# FPGA_FPGA.net
KiCad netlist of a schematic drawn in Altium Designer
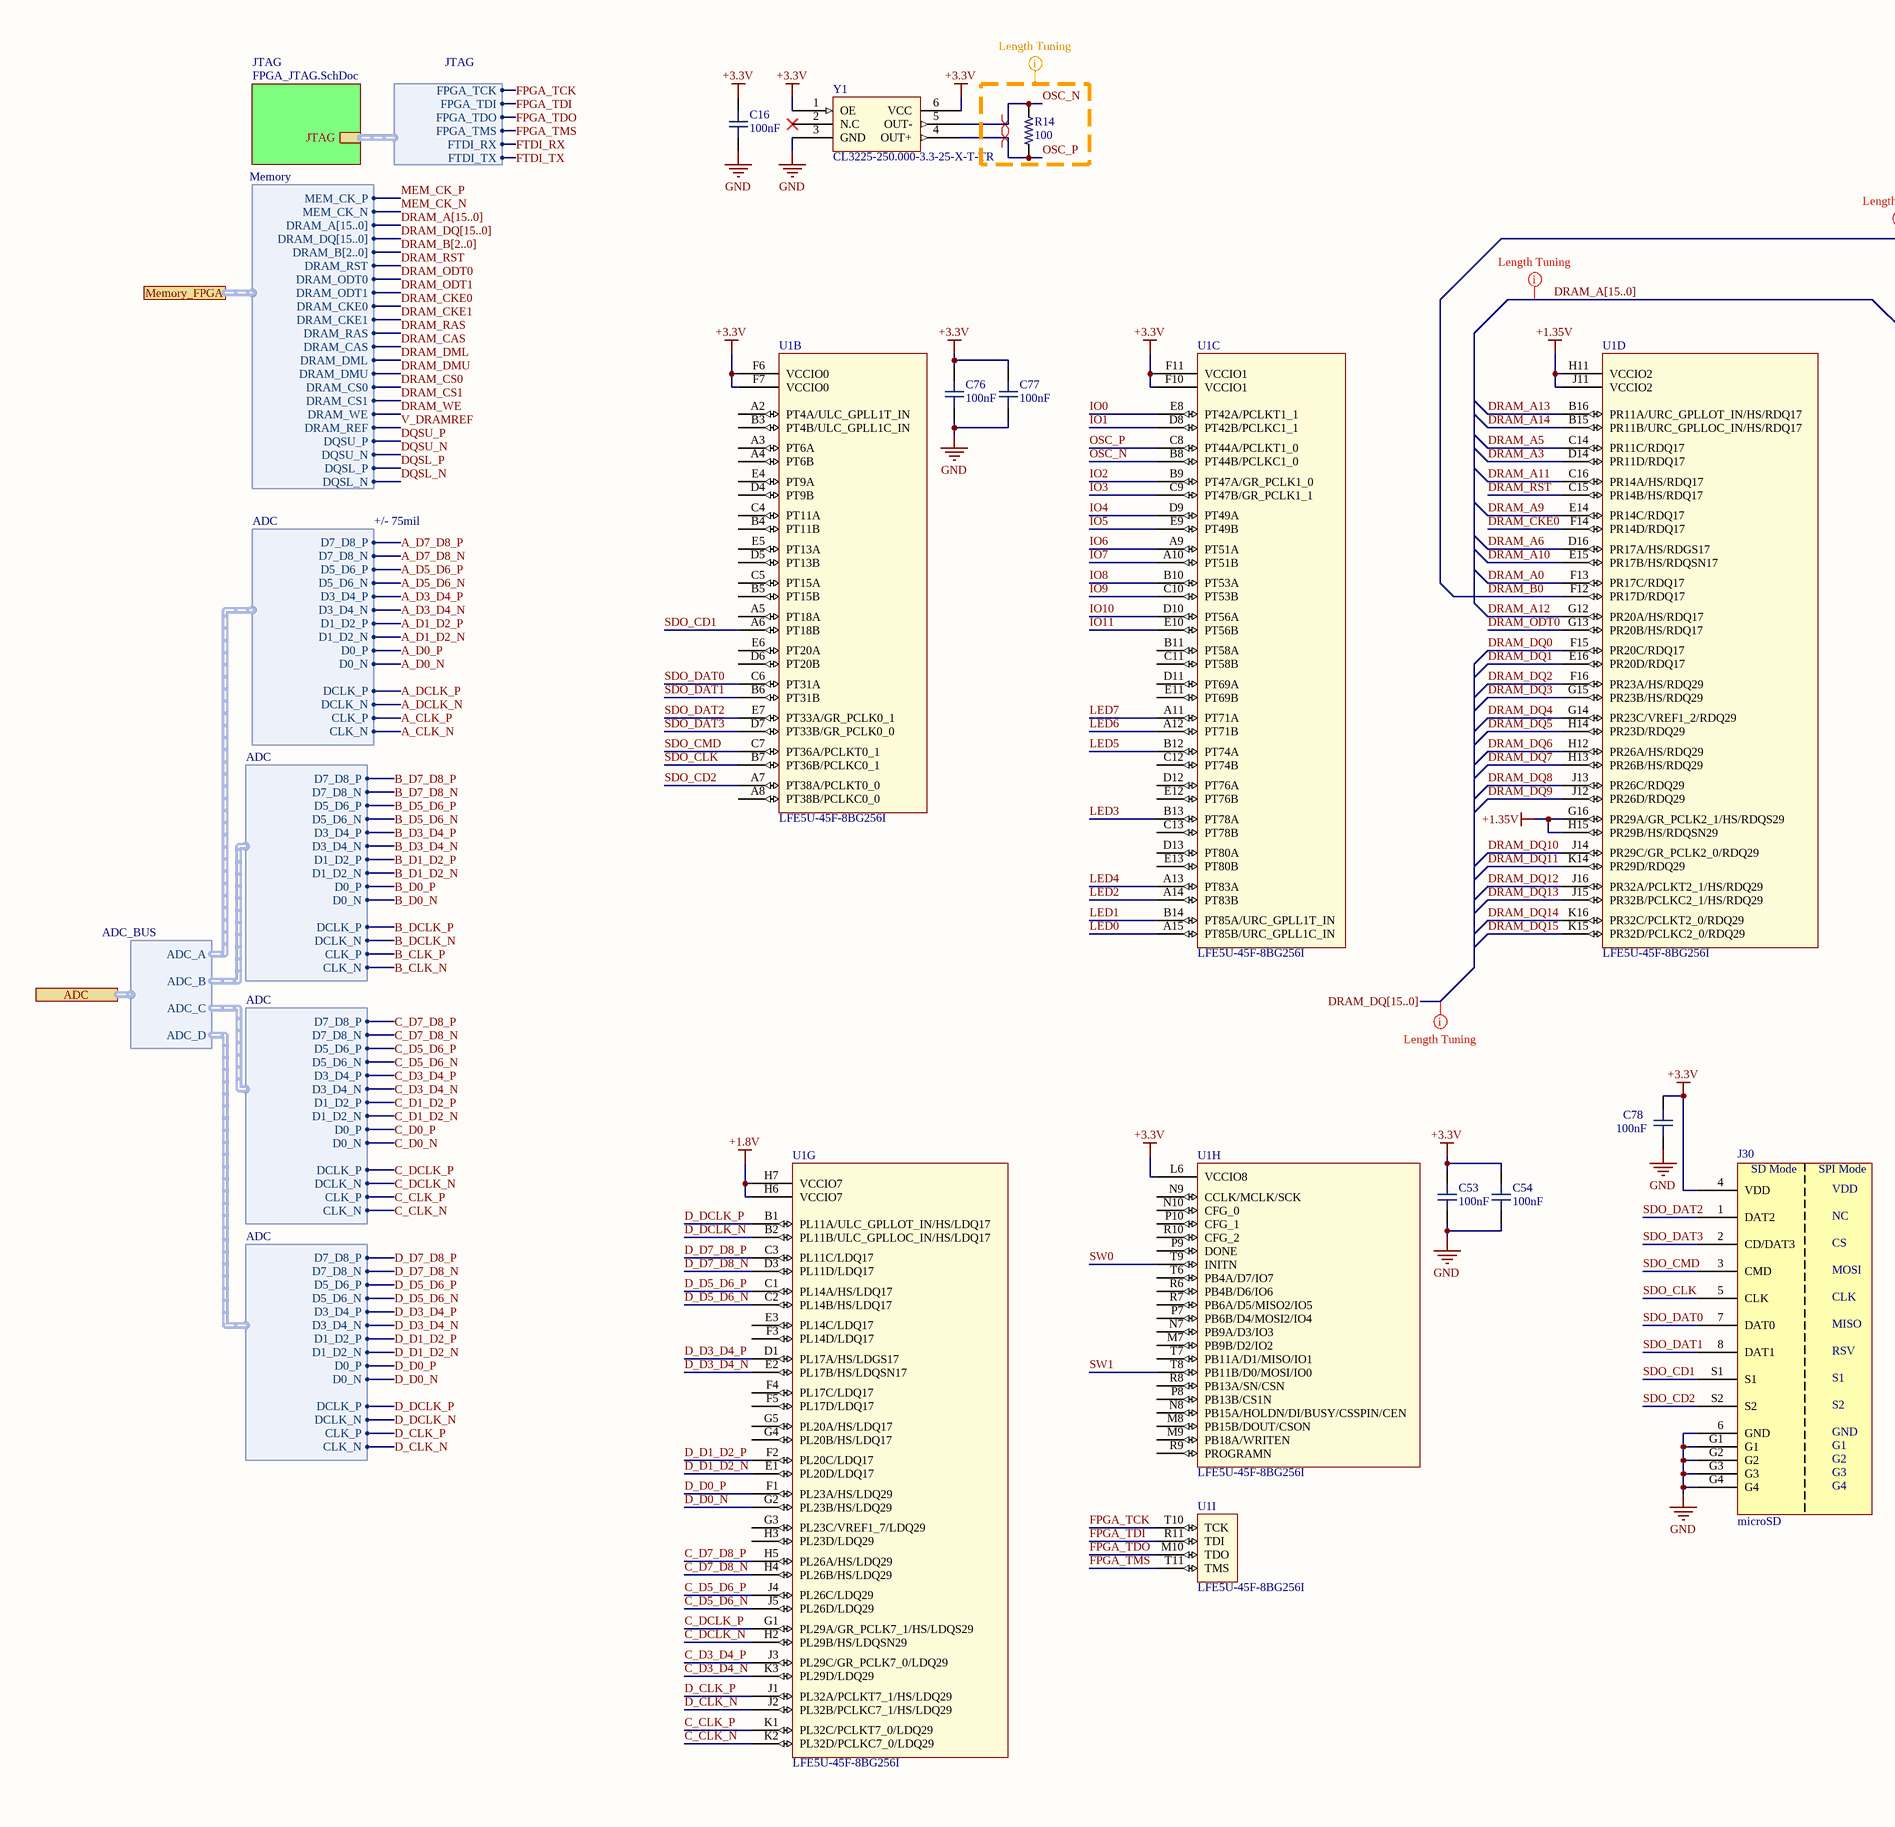
[diagram p0: FPGA_FPGA.SchDoc, left]
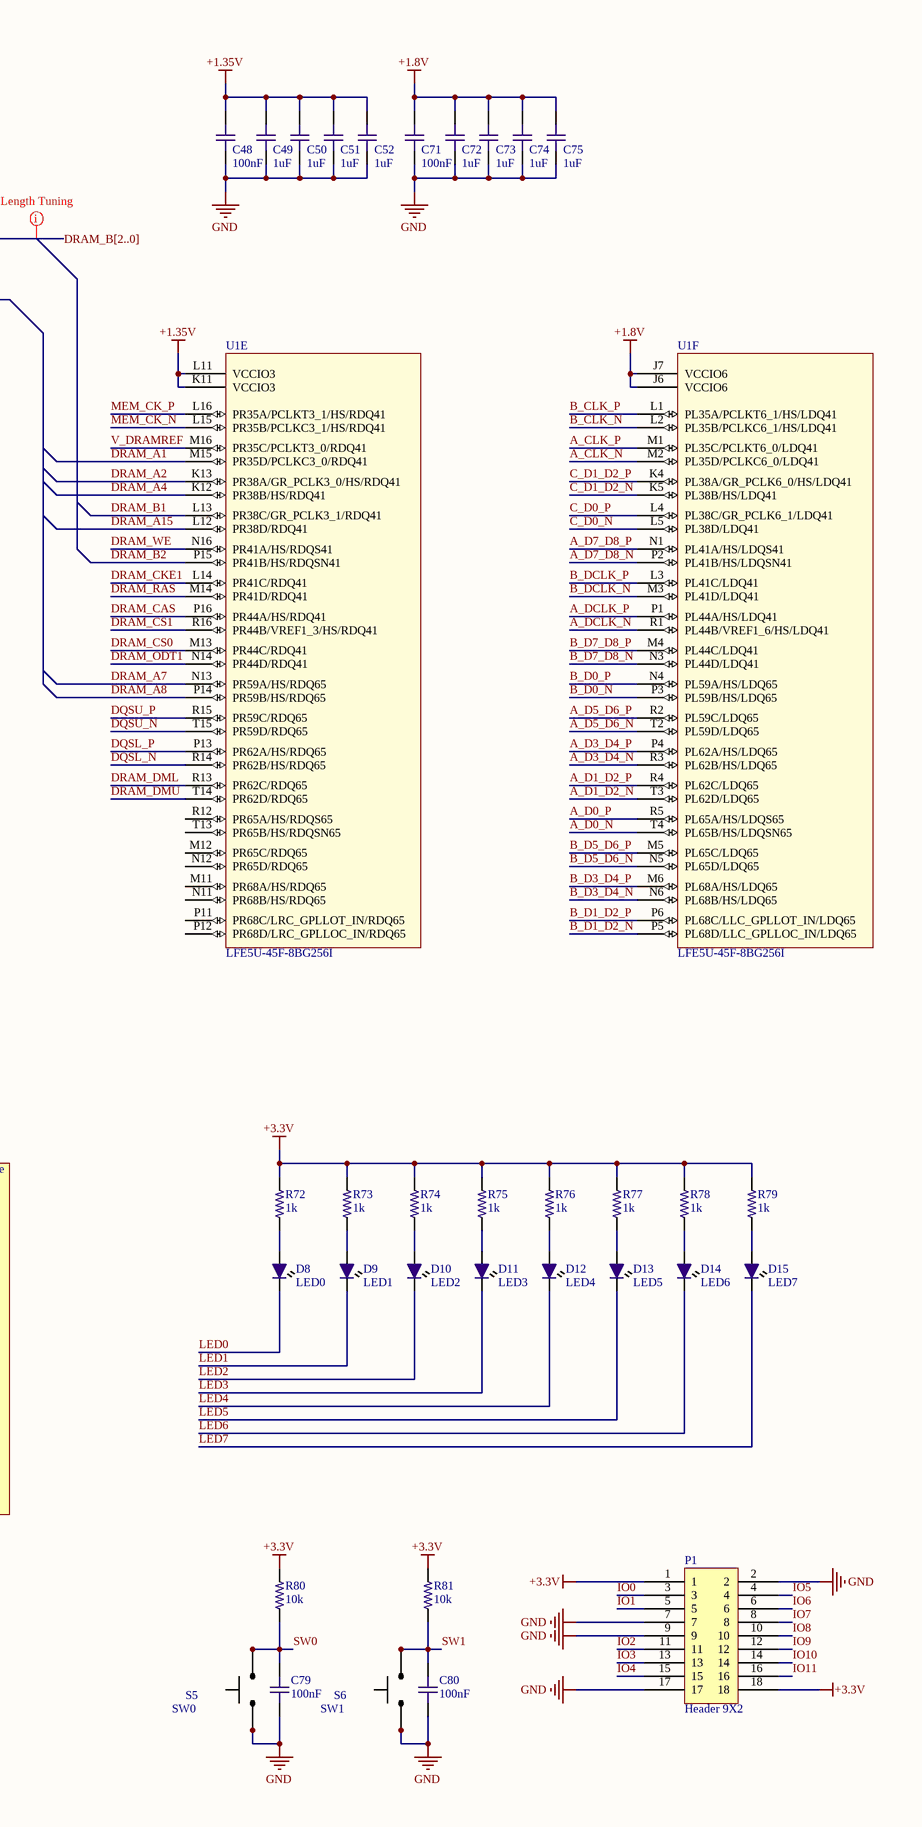
[diagram p1: FPGA_FPGA.SchDoc, right]

(export (version "E")
  (design (tool "Eeschema 10.0.6"))
  (components
    (comp (ref "C16")
      (value "100nF")
      (footprint "C0603-HIGH-DENSITY")
      (description "Chip Capacitor, 0603, 100nF, 25V, X7R")
      (fields (field (name "Comment") "C0603 100nF 25V X7R"))
      (libsource (lib "Capacitors") (part "C0603 100nF 25V X7R"))
    )
    (comp (ref "C48")
      (value "100nF")
      (footprint "C0603-HIGH-DENSITY")
      (description "Chip Capacitor, 0603, 100nF, 25V, X7R")
      (fields (field (name "Comment") "C0603 100nF 25V X7R"))
      (libsource (lib "Capacitors") (part "C0603 100nF 25V X7R"))
    )
    (comp (ref "C49")
      (value "1uF")
      (footprint "C0603-HIGH-DENSITY")
      (description "CAP CER 1UF 25V X7R 0603")
      (fields (field (name "Comment") "C0603 1uF 25V X7R"))
      (libsource (lib "Capacitors") (part "C0603 1uF 25V X7R"))
    )
    (comp (ref "C50")
      (value "1uF")
      (footprint "C0603-HIGH-DENSITY")
      (description "CAP CER 1UF 25V X7R 0603")
      (fields (field (name "Comment") "C0603 1uF 25V X7R"))
      (libsource (lib "Capacitors") (part "C0603 1uF 25V X7R"))
    )
    (comp (ref "C51")
      (value "1uF")
      (footprint "C0603-HIGH-DENSITY")
      (description "CAP CER 1UF 25V X7R 0603")
      (fields (field (name "Comment") "C0603 1uF 25V X7R"))
      (libsource (lib "Capacitors") (part "C0603 1uF 25V X7R"))
    )
    (comp (ref "C52")
      (value "1uF")
      (footprint "C0603-HIGH-DENSITY")
      (description "CAP CER 1UF 25V X7R 0603")
      (fields (field (name "Comment") "C0603 1uF 25V X7R"))
      (libsource (lib "Capacitors") (part "C0603 1uF 25V X7R"))
    )
    (comp (ref "C53")
      (value "100nF")
      (footprint "C0603-HIGH-DENSITY")
      (description "Chip Capacitor, 0603, 100nF, 25V, X7R")
      (fields (field (name "Comment") "C0603 100nF 25V X7R"))
      (libsource (lib "Capacitors") (part "C0603 100nF 25V X7R"))
    )
    (comp (ref "C54")
      (value "100nF")
      (footprint "C0603-HIGH-DENSITY")
      (description "Chip Capacitor, 0603, 100nF, 25V, X7R")
      (fields (field (name "Comment") "C0603 100nF 25V X7R"))
      (libsource (lib "Capacitors") (part "C0603 100nF 25V X7R"))
    )
    (comp (ref "C71")
      (value "100nF")
      (footprint "C0603-HIGH-DENSITY")
      (description "Chip Capacitor, 0603, 100nF, 25V, X7R")
      (fields (field (name "Comment") "C0603 100nF 25V X7R"))
      (libsource (lib "Capacitors") (part "C0603 100nF 25V X7R"))
    )
    (comp (ref "C72")
      (value "1uF")
      (footprint "C0603-HIGH-DENSITY")
      (description "CAP CER 1UF 25V X7R 0603")
      (fields (field (name "Comment") "C0603 1uF 25V X7R"))
      (libsource (lib "Capacitors") (part "C0603 1uF 25V X7R"))
    )
    (comp (ref "C73")
      (value "1uF")
      (footprint "C0603-HIGH-DENSITY")
      (description "CAP CER 1UF 25V X7R 0603")
      (fields (field (name "Comment") "C0603 1uF 25V X7R"))
      (libsource (lib "Capacitors") (part "C0603 1uF 25V X7R"))
    )
    (comp (ref "C74")
      (value "1uF")
      (footprint "C0603-HIGH-DENSITY")
      (description "CAP CER 1UF 25V X7R 0603")
      (fields (field (name "Comment") "C0603 1uF 25V X7R"))
      (libsource (lib "Capacitors") (part "C0603 1uF 25V X7R"))
    )
    (comp (ref "C75")
      (value "1uF")
      (footprint "C0603-HIGH-DENSITY")
      (description "CAP CER 1UF 25V X7R 0603")
      (fields (field (name "Comment") "C0603 1uF 25V X7R"))
      (libsource (lib "Capacitors") (part "C0603 1uF 25V X7R"))
    )
    (comp (ref "C76")
      (value "100nF")
      (footprint "C0603-HIGH-DENSITY")
      (description "Chip Capacitor, 0603, 100nF, 25V, X7R")
      (fields (field (name "Comment") "C0603 100nF 25V X7R"))
      (libsource (lib "Capacitors") (part "C0603 100nF 25V X7R"))
    )
    (comp (ref "C77")
      (value "100nF")
      (footprint "C0603-HIGH-DENSITY")
      (description "Chip Capacitor, 0603, 100nF, 25V, X7R")
      (fields (field (name "Comment") "C0603 100nF 25V X7R"))
      (libsource (lib "Capacitors") (part "C0603 100nF 25V X7R"))
    )
    (comp (ref "C78")
      (value "100nF")
      (footprint "C0603-HIGH-DENSITY")
      (description "Chip Capacitor, 0603, 100nF, 25V, X7R")
      (fields (field (name "Comment") "C0603 100nF 25V X7R"))
      (libsource (lib "Capacitors") (part "C0603 100nF 25V X7R"))
    )
    (comp (ref "C79")
      (value "100nF")
      (footprint "C0603-HIGH-DENSITY")
      (description "Chip Capacitor, 0603, 100nF, 25V, X7R")
      (fields (field (name "Comment") "C0603 100nF 25V X7R"))
      (libsource (lib "Capacitors") (part "C0603 100nF 25V X7R"))
    )
    (comp (ref "C80")
      (value "100nF")
      (footprint "C0603-HIGH-DENSITY")
      (description "Chip Capacitor, 0603, 100nF, 25V, X7R")
      (fields (field (name "Comment") "C0603 100nF 25V X7R"))
      (libsource (lib "Capacitors") (part "C0603 100nF 25V X7R"))
    )
    (comp (ref "D8")
      (value "LED0")
      (footprint "LED0603-IPC")
      (description "LED GREEN CLEAR 0603 SMD")
      (libsource (lib "Diodes") (part "LED 0603 Green"))
    )
    (comp (ref "D9")
      (value "LED1")
      (footprint "LED0603-IPC")
      (description "LED GREEN CLEAR 0603 SMD")
      (libsource (lib "Diodes") (part "LED 0603 Green"))
    )
    (comp (ref "D10")
      (value "LED2")
      (footprint "LED0603-IPC")
      (description "LED GREEN CLEAR 0603 SMD")
      (libsource (lib "Diodes") (part "LED 0603 Green"))
    )
    (comp (ref "D11")
      (value "LED3")
      (footprint "LED0603-IPC")
      (description "LED GREEN CLEAR 0603 SMD")
      (libsource (lib "Diodes") (part "LED 0603 Green"))
    )
    (comp (ref "D12")
      (value "LED4")
      (footprint "LED0603-IPC")
      (description "LED GREEN CLEAR 0603 SMD")
      (libsource (lib "Diodes") (part "LED 0603 Green"))
    )
    (comp (ref "D13")
      (value "LED5")
      (footprint "LED0603-IPC")
      (description "LED GREEN CLEAR 0603 SMD")
      (libsource (lib "Diodes") (part "LED 0603 Green"))
    )
    (comp (ref "D14")
      (value "LED6")
      (footprint "LED0603-IPC")
      (description "LED GREEN CLEAR 0603 SMD")
      (libsource (lib "Diodes") (part "LED 0603 Green"))
    )
    (comp (ref "D15")
      (value "LED7")
      (footprint "LED0603-IPC")
      (description "LED GREEN CLEAR 0603 SMD")
      (libsource (lib "Diodes") (part "LED 0603 Green"))
    )
    (comp (ref "J30")
      (value "microSD")
      (footprint "1040310811")
      (description "CONN MICRO SD CARD PUSH-PULL R/A")
      (libsource (lib "Connectors") (part "microSD"))
    )
    (comp (ref "P1")
      (value "Header 9X2")
      (footprint "Header 9X2")
      (description "0.254mm")
      (libsource (lib "Connectors") (part "Header 9X2"))
    )
    (comp (ref "R14")
      (value "100")
      (footprint "R0402-HIGH-DENSITY")
      (description "Chip Resistor, 0402, 100 ohms, 1%, 1/16 W")
      (fields (field (name "Comment") "R0402 100R 1%"))
      (libsource (lib "Resistors") (part "R0402 100R 1%"))
    )
    (comp (ref "R72")
      (value "1k")
      (footprint "R0603-IPC")
      (description "RES SMD 1K OHM 1% 1/10W 0603")
      (fields (field (name "TOLERANCE") "±1%") (field (name "Comment") "R0603 1K 1%"))
      (libsource (lib "Resistors") (part "R0603 1K 1%"))
    )
    (comp (ref "R73")
      (value "1k")
      (footprint "R0603-IPC")
      (description "RES SMD 1K OHM 1% 1/10W 0603")
      (fields (field (name "TOLERANCE") "±1%") (field (name "Comment") "R0603 1K 1%"))
      (libsource (lib "Resistors") (part "R0603 1K 1%"))
    )
    (comp (ref "R74")
      (value "1k")
      (footprint "R0603-IPC")
      (description "RES SMD 1K OHM 1% 1/10W 0603")
      (fields (field (name "TOLERANCE") "±1%") (field (name "Comment") "R0603 1K 1%"))
      (libsource (lib "Resistors") (part "R0603 1K 1%"))
    )
    (comp (ref "R75")
      (value "1k")
      (footprint "R0603-IPC")
      (description "RES SMD 1K OHM 1% 1/10W 0603")
      (fields (field (name "TOLERANCE") "±1%") (field (name "Comment") "R0603 1K 1%"))
      (libsource (lib "Resistors") (part "R0603 1K 1%"))
    )
    (comp (ref "R76")
      (value "1k")
      (footprint "R0603-IPC")
      (description "RES SMD 1K OHM 1% 1/10W 0603")
      (fields (field (name "TOLERANCE") "±1%") (field (name "Comment") "R0603 1K 1%"))
      (libsource (lib "Resistors") (part "R0603 1K 1%"))
    )
    (comp (ref "R77")
      (value "1k")
      (footprint "R0603-IPC")
      (description "RES SMD 1K OHM 1% 1/10W 0603")
      (fields (field (name "TOLERANCE") "±1%") (field (name "Comment") "R0603 1K 1%"))
      (libsource (lib "Resistors") (part "R0603 1K 1%"))
    )
    (comp (ref "R78")
      (value "1k")
      (footprint "R0603-IPC")
      (description "RES SMD 1K OHM 1% 1/10W 0603")
      (fields (field (name "TOLERANCE") "±1%") (field (name "Comment") "R0603 1K 1%"))
      (libsource (lib "Resistors") (part "R0603 1K 1%"))
    )
    (comp (ref "R79")
      (value "1k")
      (footprint "R0603-IPC")
      (description "RES SMD 1K OHM 1% 1/10W 0603")
      (fields (field (name "TOLERANCE") "±1%") (field (name "Comment") "R0603 1K 1%"))
      (libsource (lib "Resistors") (part "R0603 1K 1%"))
    )
    (comp (ref "R80")
      (value "10k")
      (footprint "R0603-IPC")
      (description "RES SMD 10K OHM 1% 1/10W 0603")
      (fields (field (name "Comment") "R0603 10K 1%"))
      (libsource (lib "Resistors") (part "R0603 10K 1%"))
    )
    (comp (ref "R81")
      (value "10k")
      (footprint "R0603-IPC")
      (description "RES SMD 10K OHM 1% 1/10W 0603")
      (fields (field (name "Comment") "R0603 10K 1%"))
      (libsource (lib "Resistors") (part "R0603 10K 1%"))
    )
    (comp (ref "S5")
      (value "SW0")
      (footprint "TL3342F260QG")
      (description "SWITCH TACTILE SPST-NO 0.05A 12V")
      (fields (field (name "MANUFACTURER PART NUMBER") "TL3342F260QG"))
      (libsource (lib "Switches") (part "SWITCH TACTILE SPST"))
    )
    (comp (ref "S6")
      (value "SW1")
      (footprint "TL3342F260QG")
      (description "SWITCH TACTILE SPST-NO 0.05A 12V")
      (fields (field (name "MANUFACTURER PART NUMBER") "TL3342F260QG"))
      (libsource (lib "Switches") (part "SWITCH TACTILE SPST"))
    )
    (comp (ref "U1")
      (value "LFE5U-45F-8BG256I")
      (footprint "caBGA256")
      (description "Lattice ECP5 45k LUTs \r\nIC FPGA 197 I/O 256CABGA")
      (libsource (lib "Integrated Circuits") (part "ECP5-45F-CABGA256"))
    )
    (comp (ref "Y1")
      (value "CL3225-250.000-3.3-25-X-T-TR")
      (footprint "Raltron CL3225")
      (description "250MHz XO (Standard) LVDS Oscillator 3.3V Enable/Disable 6-SMD, No Lead")
      (libsource (lib "Integrated Circuits") (part "CL3225-250.000-3.3-25-X-T-TR"))
    )
  )
  (nets
    (net (code "6") (name "+1.8V") (class "Default")
      (node (ref "C71") (pin "2") (pintype "passive"))
      (node (ref "C72") (pin "2") (pintype "passive"))
      (node (ref "C73") (pin "2") (pintype "passive"))
      (node (ref "C74") (pin "2") (pintype "passive"))
      (node (ref "C75") (pin "2") (pintype "passive"))
      (node (ref "U1") (pin "H6") (pinfunction "VCCIO7_H6") (pintype "power_in"))
      (node (ref "U1") (pin "H7") (pinfunction "VCCIO7_H7") (pintype "power_in"))
      (node (ref "U1") (pin "J6") (pinfunction "VCCIO6_J6") (pintype "power_in"))
      (node (ref "U1") (pin "J7") (pinfunction "VCCIO6_J7") (pintype "power_in"))
    )
    (net (code "7") (name "+1.35V") (class "Default")
      (node (ref "C48") (pin "2") (pintype "passive"))
      (node (ref "C49") (pin "2") (pintype "passive"))
      (node (ref "C50") (pin "2") (pintype "passive"))
      (node (ref "C51") (pin "2") (pintype "passive"))
      (node (ref "C52") (pin "2") (pintype "passive"))
      (node (ref "U1") (pin "G16") (pinfunction "PR29A/GR_PCLK2_1/HS/RDQS29_G16") (pintype "bidirectional"))
      (node (ref "U1") (pin "H11") (pinfunction "VCCIO2_H11") (pintype "power_in"))
      (node (ref "U1") (pin "H15") (pinfunction "PR29B/HS/RDQSN29_H15") (pintype "bidirectional"))
      (node (ref "U1") (pin "J11") (pinfunction "VCCIO2_J11") (pintype "power_in"))
      (node (ref "U1") (pin "K11") (pinfunction "VCCIO3_K11") (pintype "power_in"))
      (node (ref "U1") (pin "L11") (pinfunction "VCCIO3_L11") (pintype "power_in"))
    )
    (net (code "8") (name "+3.3V") (class "Default")
      (node (ref "C16") (pin "2") (pintype "passive"))
      (node (ref "C53") (pin "2") (pintype "passive"))
      (node (ref "C54") (pin "2") (pintype "passive"))
      (node (ref "C76") (pin "2") (pintype "passive"))
      (node (ref "C77") (pin "2") (pintype "passive"))
      (node (ref "C78") (pin "1") (pintype "passive"))
      (node (ref "J30") (pin "4") (pinfunction "VDD_4") (pintype "passive"))
      (node (ref "P1") (pin "1") (pinfunction "1_1") (pintype "passive"))
      (node (ref "P1") (pin "18") (pinfunction "18_18") (pintype "passive"))
      (node (ref "R72") (pin "2") (pintype "passive"))
      (node (ref "R73") (pin "2") (pintype "passive"))
      (node (ref "R74") (pin "2") (pintype "passive"))
      (node (ref "R75") (pin "2") (pintype "passive"))
      (node (ref "R76") (pin "2") (pintype "passive"))
      (node (ref "R77") (pin "2") (pintype "passive"))
      (node (ref "R78") (pin "2") (pintype "passive"))
      (node (ref "R79") (pin "2") (pintype "passive"))
      (node (ref "R80") (pin "2") (pintype "passive"))
      (node (ref "R81") (pin "2") (pintype "passive"))
      (node (ref "U1") (pin "F10") (pinfunction "VCCIO1_F10") (pintype "power_in"))
      (node (ref "U1") (pin "F11") (pinfunction "VCCIO1_F11") (pintype "power_in"))
      (node (ref "U1") (pin "F6") (pinfunction "VCCIO0_F6") (pintype "power_in"))
      (node (ref "U1") (pin "F7") (pinfunction "VCCIO0_F7") (pintype "power_in"))
      (node (ref "U1") (pin "L6") (pinfunction "VCCIO8_L6") (pintype "power_in"))
      (node (ref "Y1") (pin "1") (pinfunction "OE_1") (pintype "input"))
      (node (ref "Y1") (pin "6") (pinfunction "VCC_6") (pintype "passive"))
    )
    (net (code "10") (name "/A_CLK_N") (class "Default")
      (node (ref "U1") (pin "M2") (pinfunction "PL35D/PCLKC6_0/LDQ41_M2") (pintype "bidirectional"))
    )
    (net (code "11") (name "/A_CLK_P") (class "Default")
      (node (ref "U1") (pin "M1") (pinfunction "PL35C/PCLKT6_0/LDQ41_M1") (pintype "bidirectional"))
    )
    (net (code "12") (name "/A_D0_N") (class "Default")
      (node (ref "U1") (pin "T4") (pinfunction "PL65B/HS/LDQSN65_T4") (pintype "bidirectional"))
    )
    (net (code "13") (name "/A_D0_P") (class "Default")
      (node (ref "U1") (pin "R5") (pinfunction "PL65A/HS/LDQS65_R5") (pintype "bidirectional"))
    )
    (net (code "14") (name "/A_D1_D2_N") (class "Default")
      (node (ref "U1") (pin "T3") (pinfunction "PL62D/LDQ65_T3") (pintype "bidirectional"))
    )
    (net (code "15") (name "/A_D1_D2_P") (class "Default")
      (node (ref "U1") (pin "R4") (pinfunction "PL62C/LDQ65_R4") (pintype "bidirectional"))
    )
    (net (code "16") (name "/A_D3_D4_N") (class "Default")
      (node (ref "U1") (pin "R3") (pinfunction "PL62B/HS/LDQ65_R3") (pintype "bidirectional"))
    )
    (net (code "17") (name "/A_D3_D4_P") (class "Default")
      (node (ref "U1") (pin "P4") (pinfunction "PL62A/HS/LDQ65_P4") (pintype "bidirectional"))
    )
    (net (code "18") (name "/A_D5_D6_N") (class "Default")
      (node (ref "U1") (pin "T2") (pinfunction "PL59D/LDQ65_T2") (pintype "bidirectional"))
    )
    (net (code "19") (name "/A_D5_D6_P") (class "Default")
      (node (ref "U1") (pin "R2") (pinfunction "PL59C/LDQ65_R2") (pintype "bidirectional"))
    )
    (net (code "20") (name "/A_D7_D8_N") (class "Default")
      (node (ref "U1") (pin "P2") (pinfunction "PL41B/HS/LDQSN41_P2") (pintype "bidirectional"))
    )
    (net (code "21") (name "/A_D7_D8_P") (class "Default")
      (node (ref "U1") (pin "N1") (pinfunction "PL41A/HS/LDQS41_N1") (pintype "bidirectional"))
    )
    (net (code "22") (name "/A_DCLK_N") (class "Default")
      (node (ref "U1") (pin "R1") (pinfunction "PL44B/VREF1_6/HS/LDQ41_R1") (pintype "bidirectional"))
    )
    (net (code "23") (name "/A_DCLK_P") (class "Default")
      (node (ref "U1") (pin "P1") (pinfunction "PL44A/HS/LDQ41_P1") (pintype "bidirectional"))
    )
    (net (code "24") (name "/B_CLK_N") (class "Default")
      (node (ref "U1") (pin "L2") (pinfunction "PL35B/PCLKC6_1/HS/LDQ41_L2") (pintype "bidirectional"))
    )
    (net (code "25") (name "/B_CLK_P") (class "Default")
      (node (ref "U1") (pin "L1") (pinfunction "PL35A/PCLKT6_1/HS/LDQ41_L1") (pintype "bidirectional"))
    )
    (net (code "26") (name "/B_D0_N") (class "Default")
      (node (ref "U1") (pin "P3") (pinfunction "PL59B/HS/LDQ65_P3") (pintype "bidirectional"))
    )
    (net (code "27") (name "/B_D0_P") (class "Default")
      (node (ref "U1") (pin "N4") (pinfunction "PL59A/HS/LDQ65_N4") (pintype "bidirectional"))
    )
    (net (code "28") (name "/B_D1_D2_N") (class "Default")
      (node (ref "U1") (pin "P5") (pinfunction "PL68D/LLC_GPLLOC_IN/LDQ65_P5") (pintype "bidirectional"))
    )
    (net (code "29") (name "/B_D1_D2_P") (class "Default")
      (node (ref "U1") (pin "P6") (pinfunction "PL68C/LLC_GPLLOT_IN/LDQ65_P6") (pintype "bidirectional"))
    )
    (net (code "30") (name "/B_D3_D4_N") (class "Default")
      (node (ref "U1") (pin "N6") (pinfunction "PL68B/HS/LDQ65_N6") (pintype "bidirectional"))
    )
    (net (code "31") (name "/B_D3_D4_P") (class "Default")
      (node (ref "U1") (pin "M6") (pinfunction "PL68A/HS/LDQ65_M6") (pintype "bidirectional"))
    )
    (net (code "32") (name "/B_D5_D6_N") (class "Default")
      (node (ref "U1") (pin "N5") (pinfunction "PL65D/LDQ65_N5") (pintype "bidirectional"))
    )
    (net (code "33") (name "/B_D5_D6_P") (class "Default")
      (node (ref "U1") (pin "M5") (pinfunction "PL65C/LDQ65_M5") (pintype "bidirectional"))
    )
    (net (code "34") (name "/B_D7_D8_N") (class "Default")
      (node (ref "U1") (pin "N3") (pinfunction "PL44D/LDQ41_N3") (pintype "bidirectional"))
    )
    (net (code "35") (name "/B_D7_D8_P") (class "Default")
      (node (ref "U1") (pin "M4") (pinfunction "PL44C/LDQ41_M4") (pintype "bidirectional"))
    )
    (net (code "36") (name "/B_DCLK_N") (class "Default")
      (node (ref "U1") (pin "M3") (pinfunction "PL41D/LDQ41_M3") (pintype "bidirectional"))
    )
    (net (code "37") (name "/B_DCLK_P") (class "Default")
      (node (ref "U1") (pin "L3") (pinfunction "PL41C/LDQ41_L3") (pintype "bidirectional"))
    )
    (net (code "38") (name "/C_CLK_N") (class "Default")
      (node (ref "U1") (pin "K2") (pinfunction "PL32D/PCLKC7_0/LDQ29_K2") (pintype "bidirectional"))
    )
    (net (code "39") (name "/C_CLK_P") (class "Default")
      (node (ref "U1") (pin "K1") (pinfunction "PL32C/PCLKT7_0/LDQ29_K1") (pintype "bidirectional"))
    )
    (net (code "40") (name "/C_D0_N") (class "Default")
      (node (ref "U1") (pin "L5") (pinfunction "PL38D/LDQ41_L5") (pintype "bidirectional"))
    )
    (net (code "41") (name "/C_D0_P") (class "Default")
      (node (ref "U1") (pin "L4") (pinfunction "PL38C/GR_PCLK6_1/LDQ41_L4") (pintype "bidirectional"))
    )
    (net (code "42") (name "/C_D1_D2_N") (class "Default")
      (node (ref "U1") (pin "K5") (pinfunction "PL38B/HS/LDQ41_K5") (pintype "bidirectional"))
    )
    (net (code "43") (name "/C_D1_D2_P") (class "Default")
      (node (ref "U1") (pin "K4") (pinfunction "PL38A/GR_PCLK6_0/HS/LDQ41_K4") (pintype "bidirectional"))
    )
    (net (code "44") (name "/C_D3_D4_N") (class "Default")
      (node (ref "U1") (pin "K3") (pinfunction "PL29D/LDQ29_K3") (pintype "bidirectional"))
    )
    (net (code "45") (name "/C_D3_D4_P") (class "Default")
      (node (ref "U1") (pin "J3") (pinfunction "PL29C/GR_PCLK7_0/LDQ29_J3") (pintype "bidirectional"))
    )
    (net (code "46") (name "/C_D5_D6_N") (class "Default")
      (node (ref "U1") (pin "J5") (pinfunction "PL26D/LDQ29_J5") (pintype "bidirectional"))
    )
    (net (code "47") (name "/C_D5_D6_P") (class "Default")
      (node (ref "U1") (pin "J4") (pinfunction "PL26C/LDQ29_J4") (pintype "bidirectional"))
    )
    (net (code "48") (name "/C_D7_D8_N") (class "Default")
      (node (ref "U1") (pin "H4") (pinfunction "PL26B/HS/LDQ29_H4") (pintype "bidirectional"))
    )
    (net (code "49") (name "/C_D7_D8_P") (class "Default")
      (node (ref "U1") (pin "H5") (pinfunction "PL26A/HS/LDQ29_H5") (pintype "bidirectional"))
    )
    (net (code "50") (name "/C_DCLK_N") (class "Default")
      (node (ref "U1") (pin "H2") (pinfunction "PL29B/HS/LDQSN29_H2") (pintype "bidirectional"))
    )
    (net (code "51") (name "/C_DCLK_P") (class "Default")
      (node (ref "U1") (pin "G1") (pinfunction "PL29A/GR_PCLK7_1/HS/LDQS29_G1") (pintype "bidirectional"))
    )
    (net (code "52") (name "/DQSL_N") (class "Default")
      (node (ref "U1") (pin "R14") (pinfunction "PR62B/HS/RDQ65_R14") (pintype "bidirectional"))
    )
    (net (code "53") (name "/DQSL_P") (class "Default")
      (node (ref "U1") (pin "P13") (pinfunction "PR62A/HS/RDQ65_P13") (pintype "bidirectional"))
    )
    (net (code "54") (name "/DQSU_N") (class "Default")
      (node (ref "U1") (pin "T15") (pinfunction "PR59D/RDQ65_T15") (pintype "bidirectional"))
    )
    (net (code "55") (name "/DQSU_P") (class "Default")
      (node (ref "U1") (pin "R15") (pinfunction "PR59C/RDQ65_R15") (pintype "bidirectional"))
    )
    (net (code "56") (name "/DRAM_A0") (class "Default")
      (node (ref "U1") (pin "F13") (pinfunction "PR17C/RDQ17_F13") (pintype "bidirectional"))
    )
    (net (code "57") (name "/DRAM_A1") (class "Default")
      (node (ref "U1") (pin "M15") (pinfunction "PR35D/PCLKC3_0/RDQ41_M15") (pintype "bidirectional"))
    )
    (net (code "58") (name "/DRAM_A2") (class "Default")
      (node (ref "U1") (pin "K13") (pinfunction "PR38A/GR_PCLK3_0/HS/RDQ41_K13") (pintype "bidirectional"))
    )
    (net (code "59") (name "/DRAM_A3") (class "Default")
      (node (ref "U1") (pin "D14") (pinfunction "PR11D/RDQ17_D14") (pintype "bidirectional"))
    )
    (net (code "60") (name "/DRAM_A4") (class "Default")
      (node (ref "U1") (pin "K12") (pinfunction "PR38B/HS/RDQ41_K12") (pintype "bidirectional"))
    )
    (net (code "61") (name "/DRAM_A5") (class "Default")
      (node (ref "U1") (pin "C14") (pinfunction "PR11C/RDQ17_C14") (pintype "bidirectional"))
    )
    (net (code "62") (name "/DRAM_A6") (class "Default")
      (node (ref "U1") (pin "D16") (pinfunction "PR17A/HS/RDGS17_D16") (pintype "bidirectional"))
    )
    (net (code "63") (name "/DRAM_A7") (class "Default")
      (node (ref "U1") (pin "N13") (pinfunction "PR59A/HS/RDQ65_N13") (pintype "bidirectional"))
    )
    (net (code "64") (name "/DRAM_A8") (class "Default")
      (node (ref "U1") (pin "P14") (pinfunction "PR59B/HS/RDQ65_P14") (pintype "bidirectional"))
    )
    (net (code "65") (name "/DRAM_A9") (class "Default")
      (node (ref "U1") (pin "E14") (pinfunction "PR14C/RDQ17_E14") (pintype "bidirectional"))
    )
    (net (code "66") (name "/DRAM_A10") (class "Default")
      (node (ref "U1") (pin "E15") (pinfunction "PR17B/HS/RDQSN17_E15") (pintype "bidirectional"))
    )
    (net (code "67") (name "/DRAM_A11") (class "Default")
      (node (ref "U1") (pin "C16") (pinfunction "PR14A/HS/RDQ17_C16") (pintype "bidirectional"))
    )
    (net (code "68") (name "/DRAM_A12") (class "Default")
      (node (ref "U1") (pin "G12") (pinfunction "PR20A/HS/RDQ17_G12") (pintype "bidirectional"))
    )
    (net (code "69") (name "/DRAM_A13") (class "Default")
      (node (ref "U1") (pin "B16") (pinfunction "PR11A/URC_GPLLOT_IN/HS/RDQ17_B16") (pintype "bidirectional"))
    )
    (net (code "70") (name "/DRAM_A14") (class "Default")
      (node (ref "U1") (pin "B15") (pinfunction "PR11B/URC_GPLLOC_IN/HS/RDQ17_B15") (pintype "bidirectional"))
    )
    (net (code "71") (name "/DRAM_A15") (class "Default")
      (node (ref "U1") (pin "L12") (pinfunction "PR38D/RDQ41_L12") (pintype "bidirectional"))
    )
    (net (code "73") (name "/DRAM_B0") (class "Default")
      (node (ref "U1") (pin "F12") (pinfunction "PR17D/RDQ17_F12") (pintype "bidirectional"))
    )
    (net (code "74") (name "/DRAM_B1") (class "Default")
      (node (ref "U1") (pin "L13") (pinfunction "PR38C/GR_PCLK3_1/RDQ41_L13") (pintype "bidirectional"))
    )
    (net (code "75") (name "/DRAM_B2") (class "Default")
      (node (ref "U1") (pin "P15") (pinfunction "PR41B/HS/RDQSN41_P15") (pintype "bidirectional"))
    )
    (net (code "77") (name "/DRAM_CAS") (class "Default")
      (node (ref "U1") (pin "P16") (pinfunction "PR44A/HS/RDQ41_P16") (pintype "bidirectional"))
    )
    (net (code "78") (name "/DRAM_CKE0") (class "Default")
      (node (ref "U1") (pin "F14") (pinfunction "PR14D/RDQ17_F14") (pintype "bidirectional"))
    )
    (net (code "79") (name "/DRAM_CKE1") (class "Default")
      (node (ref "U1") (pin "L14") (pinfunction "PR41C/RDQ41_L14") (pintype "bidirectional"))
    )
    (net (code "80") (name "/DRAM_CS0") (class "Default")
      (node (ref "U1") (pin "M13") (pinfunction "PR44C/RDQ41_M13") (pintype "bidirectional"))
    )
    (net (code "81") (name "/DRAM_CS1") (class "Default")
      (node (ref "U1") (pin "R16") (pinfunction "PR44B/VREF1_3/HS/RDQ41_R16") (pintype "bidirectional"))
    )
    (net (code "82") (name "/DRAM_DML") (class "Default")
      (node (ref "U1") (pin "R13") (pinfunction "PR62C/RDQ65_R13") (pintype "bidirectional"))
    )
    (net (code "83") (name "/DRAM_DMU") (class "Default")
      (node (ref "U1") (pin "T14") (pinfunction "PR62D/RDQ65_T14") (pintype "bidirectional"))
    )
    (net (code "84") (name "/DRAM_DQ0") (class "Default")
      (node (ref "U1") (pin "F15") (pinfunction "PR20C/RDQ17_F15") (pintype "bidirectional"))
    )
    (net (code "85") (name "/DRAM_DQ1") (class "Default")
      (node (ref "U1") (pin "E16") (pinfunction "PR20D/RDQ17_E16") (pintype "bidirectional"))
    )
    (net (code "86") (name "/DRAM_DQ2") (class "Default")
      (node (ref "U1") (pin "F16") (pinfunction "PR23A/HS/RDQ29_F16") (pintype "bidirectional"))
    )
    (net (code "87") (name "/DRAM_DQ3") (class "Default")
      (node (ref "U1") (pin "G15") (pinfunction "PR23B/HS/RDQ29_G15") (pintype "bidirectional"))
    )
    (net (code "88") (name "/DRAM_DQ4") (class "Default")
      (node (ref "U1") (pin "G14") (pinfunction "PR23C/VREF1_2/RDQ29_G14") (pintype "bidirectional"))
    )
    (net (code "89") (name "/DRAM_DQ5") (class "Default")
      (node (ref "U1") (pin "H14") (pinfunction "PR23D/RDQ29_H14") (pintype "bidirectional"))
    )
    (net (code "90") (name "/DRAM_DQ6") (class "Default")
      (node (ref "U1") (pin "H12") (pinfunction "PR26A/HS/RDQ29_H12") (pintype "bidirectional"))
    )
    (net (code "91") (name "/DRAM_DQ7") (class "Default")
      (node (ref "U1") (pin "H13") (pinfunction "PR26B/HS/RDQ29_H13") (pintype "bidirectional"))
    )
    (net (code "92") (name "/DRAM_DQ8") (class "Default")
      (node (ref "U1") (pin "J13") (pinfunction "PR26C/RDQ29_J13") (pintype "bidirectional"))
    )
    (net (code "93") (name "/DRAM_DQ9") (class "Default")
      (node (ref "U1") (pin "J12") (pinfunction "PR26D/RDQ29_J12") (pintype "bidirectional"))
    )
    (net (code "94") (name "/DRAM_DQ10") (class "Default")
      (node (ref "U1") (pin "J14") (pinfunction "PR29C/GR_PCLK2_0/RDQ29_J14") (pintype "bidirectional"))
    )
    (net (code "95") (name "/DRAM_DQ11") (class "Default")
      (node (ref "U1") (pin "K14") (pinfunction "PR29D/RDQ29_K14") (pintype "bidirectional"))
    )
    (net (code "96") (name "/DRAM_DQ12") (class "Default")
      (node (ref "U1") (pin "J16") (pinfunction "PR32A/PCLKT2_1/HS/RDQ29_J16") (pintype "bidirectional"))
    )
    (net (code "97") (name "/DRAM_DQ13") (class "Default")
      (node (ref "U1") (pin "J15") (pinfunction "PR32B/PCLKC2_1/HS/RDQ29_J15") (pintype "bidirectional"))
    )
    (net (code "98") (name "/DRAM_DQ14") (class "Default")
      (node (ref "U1") (pin "K16") (pinfunction "PR32C/PCLKT2_0/RDQ29_K16") (pintype "bidirectional"))
    )
    (net (code "99") (name "/DRAM_DQ15") (class "Default")
      (node (ref "U1") (pin "K15") (pinfunction "PR32D/PCLKC2_0/RDQ29_K15") (pintype "bidirectional"))
    )
    (net (code "101") (name "/DRAM_ODT0") (class "Default")
      (node (ref "U1") (pin "G13") (pinfunction "PR20B/HS/RDQ17_G13") (pintype "bidirectional"))
    )
    (net (code "102") (name "/DRAM_ODT1") (class "Default")
      (node (ref "U1") (pin "N14") (pinfunction "PR44D/RDQ41_N14") (pintype "bidirectional"))
    )
    (net (code "103") (name "/DRAM_RAS") (class "Default")
      (node (ref "U1") (pin "M14") (pinfunction "PR41D/RDQ41_M14") (pintype "bidirectional"))
    )
    (net (code "104") (name "/DRAM_RST") (class "Default")
      (node (ref "U1") (pin "C15") (pinfunction "PR14B/HS/RDQ17_C15") (pintype "bidirectional"))
    )
    (net (code "105") (name "/DRAM_WE") (class "Default")
      (node (ref "U1") (pin "N16") (pinfunction "PR41A/HS/RDQS41_N16") (pintype "bidirectional"))
    )
    (net (code "106") (name "/D_CLK_N") (class "Default")
      (node (ref "U1") (pin "J2") (pinfunction "PL32B/PCLKC7_1/HS/LDQ29_J2") (pintype "bidirectional"))
    )
    (net (code "107") (name "/D_CLK_P") (class "Default")
      (node (ref "U1") (pin "J1") (pinfunction "PL32A/PCLKT7_1/HS/LDQ29_J1") (pintype "bidirectional"))
    )
    (net (code "108") (name "/D_D0_N") (class "Default")
      (node (ref "U1") (pin "G2") (pinfunction "PL23B/HS/LDQ29_G2") (pintype "bidirectional"))
    )
    (net (code "109") (name "/D_D0_P") (class "Default")
      (node (ref "U1") (pin "F1") (pinfunction "PL23A/HS/LDQ29_F1") (pintype "bidirectional"))
    )
    (net (code "110") (name "/D_D1_D2_N") (class "Default")
      (node (ref "U1") (pin "E1") (pinfunction "PL20D/LDQ17_E1") (pintype "bidirectional"))
    )
    (net (code "111") (name "/D_D1_D2_P") (class "Default")
      (node (ref "U1") (pin "F2") (pinfunction "PL20C/LDQ17_F2") (pintype "bidirectional"))
    )
    (net (code "112") (name "/D_D3_D4_N") (class "Default")
      (node (ref "U1") (pin "E2") (pinfunction "PL17B/HS/LDQSN17_E2") (pintype "bidirectional"))
    )
    (net (code "113") (name "/D_D3_D4_P") (class "Default")
      (node (ref "U1") (pin "D1") (pinfunction "PL17A/HS/LDGS17_D1") (pintype "bidirectional"))
    )
    (net (code "114") (name "/D_D5_D6_N") (class "Default")
      (node (ref "U1") (pin "C2") (pinfunction "PL14B/HS/LDQ17_C2") (pintype "bidirectional"))
    )
    (net (code "115") (name "/D_D5_D6_P") (class "Default")
      (node (ref "U1") (pin "C1") (pinfunction "PL14A/HS/LDQ17_C1") (pintype "bidirectional"))
    )
    (net (code "116") (name "/D_D7_D8_N") (class "Default")
      (node (ref "U1") (pin "D3") (pinfunction "PL11D/LDQ17_D3") (pintype "bidirectional"))
    )
    (net (code "117") (name "/D_D7_D8_P") (class "Default")
      (node (ref "U1") (pin "C3") (pinfunction "PL11C/LDQ17_C3") (pintype "bidirectional"))
    )
    (net (code "118") (name "/D_DCLK_N") (class "Default")
      (node (ref "U1") (pin "B2") (pinfunction "PL11B/ULC_GPLLOC_IN/HS/LDQ17_B2") (pintype "bidirectional"))
    )
    (net (code "119") (name "/D_DCLK_P") (class "Default")
      (node (ref "U1") (pin "B1") (pinfunction "PL11A/ULC_GPLLOT_IN/HS/LDQ17_B1") (pintype "bidirectional"))
    )
    (net (code "120") (name "/FPGA_TCK") (class "Default")
      (node (ref "U1") (pin "T10") (pinfunction "TCK_T10") (pintype "bidirectional"))
    )
    (net (code "121") (name "/FPGA_TDI") (class "Default")
      (node (ref "U1") (pin "R11") (pinfunction "TDI_R11") (pintype "bidirectional"))
    )
    (net (code "122") (name "/FPGA_TDO") (class "Default")
      (node (ref "U1") (pin "M10") (pinfunction "TDO_M10") (pintype "bidirectional"))
    )
    (net (code "123") (name "/FPGA_TMS") (class "Default")
      (node (ref "U1") (pin "T11") (pinfunction "TMS_T11") (pintype "bidirectional"))
    )
    (net (code "126") (name "/IO0") (class "Default")
      (node (ref "P1") (pin "3") (pinfunction "3_3") (pintype "passive"))
      (node (ref "U1") (pin "E8") (pinfunction "PT42A/PCLKT1_1_E8") (pintype "bidirectional"))
    )
    (net (code "127") (name "/IO1") (class "Default")
      (node (ref "P1") (pin "5") (pinfunction "5_5") (pintype "passive"))
      (node (ref "U1") (pin "D8") (pinfunction "PT42B/PCLKC1_1_D8") (pintype "bidirectional"))
    )
    (net (code "128") (name "/IO2") (class "Default")
      (node (ref "P1") (pin "11") (pinfunction "11_11") (pintype "passive"))
      (node (ref "U1") (pin "B9") (pinfunction "PT47A/GR_PCLK1_0_B9") (pintype "bidirectional"))
    )
    (net (code "129") (name "/IO3") (class "Default")
      (node (ref "P1") (pin "13") (pinfunction "13_13") (pintype "passive"))
      (node (ref "U1") (pin "C9") (pinfunction "PT47B/GR_PCLK1_1_C9") (pintype "bidirectional"))
    )
    (net (code "130") (name "/IO4") (class "Default")
      (node (ref "P1") (pin "15") (pinfunction "15_15") (pintype "passive"))
      (node (ref "U1") (pin "D9") (pinfunction "PT49A_D9") (pintype "bidirectional"))
    )
    (net (code "131") (name "/IO5") (class "Default")
      (node (ref "P1") (pin "4") (pinfunction "4_4") (pintype "passive"))
      (node (ref "U1") (pin "E9") (pinfunction "PT49B_E9") (pintype "bidirectional"))
    )
    (net (code "132") (name "/IO6") (class "Default")
      (node (ref "P1") (pin "6") (pinfunction "6_6") (pintype "passive"))
      (node (ref "U1") (pin "A9") (pinfunction "PT51A_A9") (pintype "bidirectional"))
    )
    (net (code "133") (name "/IO7") (class "Default")
      (node (ref "P1") (pin "8") (pinfunction "8_8") (pintype "passive"))
      (node (ref "U1") (pin "A10") (pinfunction "PT51B_A10") (pintype "bidirectional"))
    )
    (net (code "134") (name "/IO8") (class "Default")
      (node (ref "P1") (pin "10") (pinfunction "10_10") (pintype "passive"))
      (node (ref "U1") (pin "B10") (pinfunction "PT53A_B10") (pintype "bidirectional"))
    )
    (net (code "135") (name "/IO9") (class "Default")
      (node (ref "P1") (pin "12") (pinfunction "12_12") (pintype "passive"))
      (node (ref "U1") (pin "C10") (pinfunction "PT53B_C10") (pintype "bidirectional"))
    )
    (net (code "136") (name "/IO10") (class "Default")
      (node (ref "P1") (pin "14") (pinfunction "14_14") (pintype "passive"))
      (node (ref "U1") (pin "D10") (pinfunction "PT56A_D10") (pintype "bidirectional"))
    )
    (net (code "137") (name "/IO11") (class "Default")
      (node (ref "P1") (pin "16") (pinfunction "16_16") (pintype "passive"))
      (node (ref "U1") (pin "E10") (pinfunction "PT56B_E10") (pintype "bidirectional"))
    )
    (net (code "138") (name "/LED0") (class "Default")
      (node (ref "D8") (pin "K") (pintype "passive"))
      (node (ref "U1") (pin "A15") (pinfunction "PT85B/URC_GPLL1C_IN_A15") (pintype "bidirectional"))
    )
    (net (code "139") (name "/LED1") (class "Default")
      (node (ref "D9") (pin "K") (pintype "passive"))
      (node (ref "U1") (pin "B14") (pinfunction "PT85A/URC_GPLL1T_IN_B14") (pintype "bidirectional"))
    )
    (net (code "140") (name "/LED2") (class "Default")
      (node (ref "D10") (pin "K") (pintype "passive"))
      (node (ref "U1") (pin "A14") (pinfunction "PT83B_A14") (pintype "bidirectional"))
    )
    (net (code "141") (name "/LED3") (class "Default")
      (node (ref "D11") (pin "K") (pintype "passive"))
      (node (ref "U1") (pin "B13") (pinfunction "PT78A_B13") (pintype "bidirectional"))
    )
    (net (code "142") (name "/LED4") (class "Default")
      (node (ref "D12") (pin "K") (pintype "passive"))
      (node (ref "U1") (pin "A13") (pinfunction "PT83A_A13") (pintype "bidirectional"))
    )
    (net (code "143") (name "/LED5") (class "Default")
      (node (ref "D13") (pin "K") (pintype "passive"))
      (node (ref "U1") (pin "B12") (pinfunction "PT74A_B12") (pintype "bidirectional"))
    )
    (net (code "144") (name "/LED6") (class "Default")
      (node (ref "D14") (pin "K") (pintype "passive"))
      (node (ref "U1") (pin "A12") (pinfunction "PT71B_A12") (pintype "bidirectional"))
    )
    (net (code "145") (name "/LED7") (class "Default")
      (node (ref "D15") (pin "K") (pintype "passive"))
      (node (ref "U1") (pin "A11") (pinfunction "PT71A_A11") (pintype "bidirectional"))
    )
    (net (code "146") (name "/MEM_CK_N") (class "Default")
      (node (ref "U1") (pin "L15") (pinfunction "PR35B/PCLKC3_1/HS/RDQ41_L15") (pintype "bidirectional"))
    )
    (net (code "147") (name "/MEM_CK_P") (class "Default")
      (node (ref "U1") (pin "L16") (pinfunction "PR35A/PCLKT3_1/HS/RDQ41_L16") (pintype "bidirectional"))
    )
    (net (code "148") (name "/OSC_N") (class "Default")
      (node (ref "R14") (pin "2") (pintype "passive"))
      (node (ref "U1") (pin "B8") (pinfunction "PT44B/PCLKC1_0_B8") (pintype "bidirectional"))
      (node (ref "Y1") (pin "5") (pinfunction "OUT-_5") (pintype "output"))
    )
    (net (code "149") (name "/OSC_P") (class "Default")
      (node (ref "R14") (pin "1") (pintype "passive"))
      (node (ref "U1") (pin "C8") (pinfunction "PT44A/PCLKT1_0_C8") (pintype "bidirectional"))
      (node (ref "Y1") (pin "4") (pinfunction "OUT+_4") (pintype "output"))
    )
    (net (code "150") (name "/SDO_CD1") (class "Default")
      (node (ref "J30") (pin "S1") (pinfunction "S1_S1") (pintype "passive"))
      (node (ref "U1") (pin "A6") (pinfunction "PT18B_A6") (pintype "bidirectional"))
    )
    (net (code "151") (name "/SDO_CD2") (class "Default")
      (node (ref "J30") (pin "S2") (pinfunction "S2_S2") (pintype "passive"))
      (node (ref "U1") (pin "A7") (pinfunction "PT38A/PCLKT0_0_A7") (pintype "bidirectional"))
    )
    (net (code "152") (name "/SDO_CLK") (class "Default")
      (node (ref "J30") (pin "5") (pinfunction "CLK_5") (pintype "passive"))
      (node (ref "U1") (pin "B7") (pinfunction "PT36B/PCLKC0_1_B7") (pintype "bidirectional"))
    )
    (net (code "153") (name "/SDO_CMD") (class "Default")
      (node (ref "J30") (pin "3") (pinfunction "CMD_3") (pintype "passive"))
      (node (ref "U1") (pin "C7") (pinfunction "PT36A/PCLKT0_1_C7") (pintype "bidirectional"))
    )
    (net (code "154") (name "/SDO_DAT0") (class "Default")
      (node (ref "J30") (pin "7") (pinfunction "DAT0_7") (pintype "passive"))
      (node (ref "U1") (pin "C6") (pinfunction "PT31A_C6") (pintype "bidirectional"))
    )
    (net (code "155") (name "/SDO_DAT1") (class "Default")
      (node (ref "J30") (pin "8") (pinfunction "DAT1_8") (pintype "passive"))
      (node (ref "U1") (pin "B6") (pinfunction "PT31B_B6") (pintype "bidirectional"))
    )
    (net (code "156") (name "/SDO_DAT2") (class "Default")
      (node (ref "J30") (pin "1") (pinfunction "DAT2_1") (pintype "passive"))
      (node (ref "U1") (pin "E7") (pinfunction "PT33A/GR_PCLK0_1_E7") (pintype "bidirectional"))
    )
    (net (code "157") (name "/SDO_DAT3") (class "Default")
      (node (ref "J30") (pin "2") (pinfunction "CD/DAT3_2") (pintype "passive"))
      (node (ref "U1") (pin "D7") (pinfunction "PT33B/GR_PCLK0_0_D7") (pintype "bidirectional"))
    )
    (net (code "158") (name "/SW0") (class "Default")
      (node (ref "C79") (pin "2") (pintype "passive"))
      (node (ref "R80") (pin "1") (pintype "passive"))
      (node (ref "S5") (pin "1") (pinfunction "1_1") (pintype "passive"))
      (node (ref "S5") (pin "2") (pinfunction "2_2") (pintype "passive"))
      (node (ref "U1") (pin "T9") (pinfunction "INITN_T9") (pintype "bidirectional"))
    )
    (net (code "159") (name "/SW1") (class "Default")
      (node (ref "C80") (pin "2") (pintype "passive"))
      (node (ref "R81") (pin "1") (pintype "passive"))
      (node (ref "S6") (pin "1") (pinfunction "1_1") (pintype "passive"))
      (node (ref "S6") (pin "2") (pinfunction "2_2") (pintype "passive"))
      (node (ref "U1") (pin "T8") (pinfunction "PB11B/D0/MOSI/IO0_T8") (pintype "bidirectional"))
    )
    (net (code "160") (name "/V_DRAMREF") (class "Default")
      (node (ref "U1") (pin "M16") (pinfunction "PR35C/PCLKT3_0/RDQ41_M16") (pintype "bidirectional"))
    )
    (net (code "165") (name "GND") (class "Default")
      (node (ref "C16") (pin "1") (pintype "passive"))
      (node (ref "C48") (pin "1") (pintype "passive"))
      (node (ref "C49") (pin "1") (pintype "passive"))
      (node (ref "C50") (pin "1") (pintype "passive"))
      (node (ref "C51") (pin "1") (pintype "passive"))
      (node (ref "C52") (pin "1") (pintype "passive"))
      (node (ref "C53") (pin "1") (pintype "passive"))
      (node (ref "C54") (pin "1") (pintype "passive"))
      (node (ref "C71") (pin "1") (pintype "passive"))
      (node (ref "C72") (pin "1") (pintype "passive"))
      (node (ref "C73") (pin "1") (pintype "passive"))
      (node (ref "C74") (pin "1") (pintype "passive"))
      (node (ref "C75") (pin "1") (pintype "passive"))
      (node (ref "C76") (pin "1") (pintype "passive"))
      (node (ref "C77") (pin "1") (pintype "passive"))
      (node (ref "C78") (pin "2") (pintype "passive"))
      (node (ref "C79") (pin "1") (pintype "passive"))
      (node (ref "C80") (pin "1") (pintype "passive"))
      (node (ref "J30") (pin "6") (pinfunction "GND_6") (pintype "passive"))
      (node (ref "J30") (pin "G1") (pinfunction "G1_G1") (pintype "passive"))
      (node (ref "J30") (pin "G2") (pinfunction "G2_G2") (pintype "passive"))
      (node (ref "J30") (pin "G3") (pinfunction "G3_G3") (pintype "passive"))
      (node (ref "J30") (pin "G4") (pinfunction "G4_G4") (pintype "passive"))
      (node (ref "P1") (pin "17") (pinfunction "17_17") (pintype "passive"))
      (node (ref "P1") (pin "2") (pinfunction "2_2") (pintype "passive"))
      (node (ref "P1") (pin "7") (pinfunction "7_7") (pintype "passive"))
      (node (ref "P1") (pin "9") (pinfunction "9_9") (pintype "passive"))
      (node (ref "S5") (pin "3") (pinfunction "3_3") (pintype "passive"))
      (node (ref "S5") (pin "4") (pinfunction "4_4") (pintype "passive"))
      (node (ref "S6") (pin "3") (pinfunction "3_3") (pintype "passive"))
      (node (ref "S6") (pin "4") (pinfunction "4_4") (pintype "passive"))
      (node (ref "Y1") (pin "3") (pinfunction "GND_3") (pintype "passive"))
    )
    (net (code "166") (name "Net-(D8-PadA)") (class "Default")
      (node (ref "D8") (pin "A") (pintype "passive"))
      (node (ref "R72") (pin "1") (pintype "passive"))
    )
    (net (code "167") (name "Net-(D9-PadA)") (class "Default")
      (node (ref "D9") (pin "A") (pintype "passive"))
      (node (ref "R73") (pin "1") (pintype "passive"))
    )
    (net (code "168") (name "Net-(D10-PadA)") (class "Default")
      (node (ref "D10") (pin "A") (pintype "passive"))
      (node (ref "R74") (pin "1") (pintype "passive"))
    )
    (net (code "169") (name "Net-(D11-PadA)") (class "Default")
      (node (ref "D11") (pin "A") (pintype "passive"))
      (node (ref "R75") (pin "1") (pintype "passive"))
    )
    (net (code "170") (name "Net-(D12-PadA)") (class "Default")
      (node (ref "D12") (pin "A") (pintype "passive"))
      (node (ref "R76") (pin "1") (pintype "passive"))
    )
    (net (code "171") (name "Net-(D13-PadA)") (class "Default")
      (node (ref "D13") (pin "A") (pintype "passive"))
      (node (ref "R77") (pin "1") (pintype "passive"))
    )
    (net (code "172") (name "Net-(D14-PadA)") (class "Default")
      (node (ref "D14") (pin "A") (pintype "passive"))
      (node (ref "R78") (pin "1") (pintype "passive"))
    )
    (net (code "173") (name "Net-(D15-PadA)") (class "Default")
      (node (ref "D15") (pin "A") (pintype "passive"))
      (node (ref "R79") (pin "1") (pintype "passive"))
    )
    (net (code "174") (name "unconnected-(U1B-PT4A{slash}ULC_GPLL1T_IN-PadA2)") (class "Default")
      (node (ref "U1") (pin "A2") (pinfunction "PT4A/ULC_GPLL1T_IN_A2") (pintype "bidirectional"))
    )
    (net (code "175") (name "unconnected-(U1B-PT4B{slash}ULC_GPLL1C_IN-PadB3)") (class "Default")
      (node (ref "U1") (pin "B3") (pinfunction "PT4B/ULC_GPLL1C_IN_B3") (pintype "bidirectional"))
    )
    (net (code "176") (name "unconnected-(U1B-PT6A-PadA3)") (class "Default")
      (node (ref "U1") (pin "A3") (pinfunction "PT6A_A3") (pintype "bidirectional"))
    )
    (net (code "177") (name "unconnected-(U1B-PT6B-PadA4)") (class "Default")
      (node (ref "U1") (pin "A4") (pinfunction "PT6B_A4") (pintype "bidirectional"))
    )
    (net (code "178") (name "unconnected-(U1B-PT9A-PadE4)") (class "Default")
      (node (ref "U1") (pin "E4") (pinfunction "PT9A_E4") (pintype "bidirectional"))
    )
    (net (code "179") (name "unconnected-(U1B-PT9B-PadD4)") (class "Default")
      (node (ref "U1") (pin "D4") (pinfunction "PT9B_D4") (pintype "bidirectional"))
    )
    (net (code "180") (name "unconnected-(U1B-PT11A-PadC4)") (class "Default")
      (node (ref "U1") (pin "C4") (pinfunction "PT11A_C4") (pintype "bidirectional"))
    )
    (net (code "181") (name "unconnected-(U1B-PT11B-PadB4)") (class "Default")
      (node (ref "U1") (pin "B4") (pinfunction "PT11B_B4") (pintype "bidirectional"))
    )
    (net (code "182") (name "unconnected-(U1B-PT13A-PadE5)") (class "Default")
      (node (ref "U1") (pin "E5") (pinfunction "PT13A_E5") (pintype "bidirectional"))
    )
    (net (code "183") (name "unconnected-(U1B-PT13B-PadD5)") (class "Default")
      (node (ref "U1") (pin "D5") (pinfunction "PT13B_D5") (pintype "bidirectional"))
    )
    (net (code "184") (name "unconnected-(U1B-PT15A-PadC5)") (class "Default")
      (node (ref "U1") (pin "C5") (pinfunction "PT15A_C5") (pintype "bidirectional"))
    )
    (net (code "185") (name "unconnected-(U1B-PT15B-PadB5)") (class "Default")
      (node (ref "U1") (pin "B5") (pinfunction "PT15B_B5") (pintype "bidirectional"))
    )
    (net (code "186") (name "unconnected-(U1B-PT18A-PadA5)") (class "Default")
      (node (ref "U1") (pin "A5") (pinfunction "PT18A_A5") (pintype "bidirectional"))
    )
    (net (code "187") (name "unconnected-(U1B-PT20A-PadE6)") (class "Default")
      (node (ref "U1") (pin "E6") (pinfunction "PT20A_E6") (pintype "bidirectional"))
    )
    (net (code "188") (name "unconnected-(U1B-PT20B-PadD6)") (class "Default")
      (node (ref "U1") (pin "D6") (pinfunction "PT20B_D6") (pintype "bidirectional"))
    )
    (net (code "189") (name "unconnected-(U1B-PT38B{slash}PCLKC0_0-PadA8)") (class "Default")
      (node (ref "U1") (pin "A8") (pinfunction "PT38B/PCLKC0_0_A8") (pintype "bidirectional"))
    )
    (net (code "190") (name "unconnected-(U1C-PT58A-PadB11)") (class "Default")
      (node (ref "U1") (pin "B11") (pinfunction "PT58A_B11") (pintype "bidirectional"))
    )
    (net (code "191") (name "unconnected-(U1C-PT58B-PadC11)") (class "Default")
      (node (ref "U1") (pin "C11") (pinfunction "PT58B_C11") (pintype "bidirectional"))
    )
    (net (code "192") (name "unconnected-(U1C-PT69A-PadD11)") (class "Default")
      (node (ref "U1") (pin "D11") (pinfunction "PT69A_D11") (pintype "bidirectional"))
    )
    (net (code "193") (name "unconnected-(U1C-PT69B-PadE11)") (class "Default")
      (node (ref "U1") (pin "E11") (pinfunction "PT69B_E11") (pintype "bidirectional"))
    )
    (net (code "194") (name "unconnected-(U1C-PT74B-PadC12)") (class "Default")
      (node (ref "U1") (pin "C12") (pinfunction "PT74B_C12") (pintype "bidirectional"))
    )
    (net (code "195") (name "unconnected-(U1C-PT76A-PadD12)") (class "Default")
      (node (ref "U1") (pin "D12") (pinfunction "PT76A_D12") (pintype "bidirectional"))
    )
    (net (code "196") (name "unconnected-(U1C-PT76B-PadE12)") (class "Default")
      (node (ref "U1") (pin "E12") (pinfunction "PT76B_E12") (pintype "bidirectional"))
    )
    (net (code "197") (name "unconnected-(U1C-PT78B-PadC13)") (class "Default")
      (node (ref "U1") (pin "C13") (pinfunction "PT78B_C13") (pintype "bidirectional"))
    )
    (net (code "198") (name "unconnected-(U1C-PT80A-PadD13)") (class "Default")
      (node (ref "U1") (pin "D13") (pinfunction "PT80A_D13") (pintype "bidirectional"))
    )
    (net (code "199") (name "unconnected-(U1C-PT80B-PadE13)") (class "Default")
      (node (ref "U1") (pin "E13") (pinfunction "PT80B_E13") (pintype "bidirectional"))
    )
    (net (code "200") (name "unconnected-(U1E-PR65A{slash}HS{slash}RDQS65-PadR12)") (class "Default")
      (node (ref "U1") (pin "R12") (pinfunction "PR65A/HS/RDQS65_R12") (pintype "bidirectional"))
    )
    (net (code "201") (name "unconnected-(U1E-PR65B{slash}HS{slash}RDQSN65-PadT13)") (class "Default")
      (node (ref "U1") (pin "T13") (pinfunction "PR65B/HS/RDQSN65_T13") (pintype "bidirectional"))
    )
    (net (code "202") (name "unconnected-(U1E-PR65C{slash}RDQ65-PadM12)") (class "Default")
      (node (ref "U1") (pin "M12") (pinfunction "PR65C/RDQ65_M12") (pintype "bidirectional"))
    )
    (net (code "203") (name "unconnected-(U1E-PR65D{slash}RDQ65-PadN12)") (class "Default")
      (node (ref "U1") (pin "N12") (pinfunction "PR65D/RDQ65_N12") (pintype "bidirectional"))
    )
    (net (code "204") (name "unconnected-(U1E-PR68A{slash}HS{slash}RDQ65-PadM11)") (class "Default")
      (node (ref "U1") (pin "M11") (pinfunction "PR68A/HS/RDQ65_M11") (pintype "bidirectional"))
    )
    (net (code "205") (name "unconnected-(U1E-PR68B{slash}HS{slash}RDQ65-PadN11)") (class "Default")
      (node (ref "U1") (pin "N11") (pinfunction "PR68B/HS/RDQ65_N11") (pintype "bidirectional"))
    )
    (net (code "206") (name "unconnected-(U1E-PR68C{slash}LRC_GPLLOT_IN{slash}RDQ65-PadP11)") (class "Default")
      (node (ref "U1") (pin "P11") (pinfunction "PR68C/LRC_GPLLOT_IN/RDQ65_P11") (pintype "bidirectional"))
    )
    (net (code "207") (name "unconnected-(U1E-PR68D{slash}LRC_GPLLOC_IN{slash}RDQ65-PadP12)") (class "Default")
      (node (ref "U1") (pin "P12") (pinfunction "PR68D/LRC_GPLLOC_IN/RDQ65_P12") (pintype "bidirectional"))
    )
    (net (code "208") (name "unconnected-(U1G-PL14C{slash}LDQ17-PadE3)") (class "Default")
      (node (ref "U1") (pin "E3") (pinfunction "PL14C/LDQ17_E3") (pintype "bidirectional"))
    )
    (net (code "209") (name "unconnected-(U1G-PL14D{slash}LDQ17-PadF3)") (class "Default")
      (node (ref "U1") (pin "F3") (pinfunction "PL14D/LDQ17_F3") (pintype "bidirectional"))
    )
    (net (code "210") (name "unconnected-(U1G-PL17C{slash}LDQ17-PadF4)") (class "Default")
      (node (ref "U1") (pin "F4") (pinfunction "PL17C/LDQ17_F4") (pintype "bidirectional"))
    )
    (net (code "211") (name "unconnected-(U1G-PL17D{slash}LDQ17-PadF5)") (class "Default")
      (node (ref "U1") (pin "F5") (pinfunction "PL17D/LDQ17_F5") (pintype "bidirectional"))
    )
    (net (code "212") (name "unconnected-(U1G-PL20A{slash}HS{slash}LDQ17-PadG5)") (class "Default")
      (node (ref "U1") (pin "G5") (pinfunction "PL20A/HS/LDQ17_G5") (pintype "bidirectional"))
    )
    (net (code "213") (name "unconnected-(U1G-PL20B{slash}HS{slash}LDQ17-PadG4)") (class "Default")
      (node (ref "U1") (pin "G4") (pinfunction "PL20B/HS/LDQ17_G4") (pintype "bidirectional"))
    )
    (net (code "214") (name "unconnected-(U1G-PL23C{slash}VREF1_7{slash}LDQ29-PadG3)") (class "Default")
      (node (ref "U1") (pin "G3") (pinfunction "PL23C/VREF1_7/LDQ29_G3") (pintype "bidirectional"))
    )
    (net (code "215") (name "unconnected-(U1G-PL23D{slash}LDQ29-PadH3)") (class "Default")
      (node (ref "U1") (pin "H3") (pinfunction "PL23D/LDQ29_H3") (pintype "bidirectional"))
    )
    (net (code "216") (name "unconnected-(U1H-CCLK{slash}MCLK{slash}SCK-PadN9)") (class "Default")
      (node (ref "U1") (pin "N9") (pinfunction "CCLK/MCLK/SCK_N9") (pintype "bidirectional"))
    )
    (net (code "217") (name "unconnected-(U1H-CFG_0-PadN10)") (class "Default")
      (node (ref "U1") (pin "N10") (pinfunction "CFG_0_N10") (pintype "bidirectional"))
    )
    (net (code "218") (name "unconnected-(U1H-CFG_1-PadP10)") (class "Default")
      (node (ref "U1") (pin "P10") (pinfunction "CFG_1_P10") (pintype "bidirectional"))
    )
    (net (code "219") (name "unconnected-(U1H-CFG_2-PadR10)") (class "Default")
      (node (ref "U1") (pin "R10") (pinfunction "CFG_2_R10") (pintype "bidirectional"))
    )
    (net (code "220") (name "unconnected-(U1H-DONE-PadP9)") (class "Default")
      (node (ref "U1") (pin "P9") (pinfunction "DONE_P9") (pintype "bidirectional"))
    )
    (net (code "221") (name "unconnected-(U1H-PB4A{slash}D7{slash}IO7-PadT6)") (class "Default")
      (node (ref "U1") (pin "T6") (pinfunction "PB4A/D7/IO7_T6") (pintype "bidirectional"))
    )
    (net (code "222") (name "unconnected-(U1H-PB4B{slash}D6{slash}IO6-PadR6)") (class "Default")
      (node (ref "U1") (pin "R6") (pinfunction "PB4B/D6/IO6_R6") (pintype "bidirectional"))
    )
    (net (code "223") (name "unconnected-(U1H-PB6A{slash}D5{slash}MISO2{slash}IO5-PadR7)") (class "Default")
      (node (ref "U1") (pin "R7") (pinfunction "PB6A/D5/MISO2/IO5_R7") (pintype "bidirectional"))
    )
    (net (code "224") (name "unconnected-(U1H-PB6B{slash}D4{slash}MOSI2{slash}IO4-PadP7)") (class "Default")
      (node (ref "U1") (pin "P7") (pinfunction "PB6B/D4/MOSI2/IO4_P7") (pintype "bidirectional"))
    )
    (net (code "225") (name "unconnected-(U1H-PB9A{slash}D3{slash}IO3-PadN7)") (class "Default")
      (node (ref "U1") (pin "N7") (pinfunction "PB9A/D3/IO3_N7") (pintype "bidirectional"))
    )
    (net (code "226") (name "unconnected-(U1H-PB9B{slash}D2{slash}IO2-PadM7)") (class "Default")
      (node (ref "U1") (pin "M7") (pinfunction "PB9B/D2/IO2_M7") (pintype "bidirectional"))
    )
    (net (code "227") (name "unconnected-(U1H-PB11A{slash}D1{slash}MISO{slash}IO1-PadT7)") (class "Default")
      (node (ref "U1") (pin "T7") (pinfunction "PB11A/D1/MISO/IO1_T7") (pintype "bidirectional"))
    )
    (net (code "228") (name "unconnected-(U1H-PB13A{slash}SN{slash}CSN-PadR8)") (class "Default")
      (node (ref "U1") (pin "R8") (pinfunction "PB13A/SN/CSN_R8") (pintype "bidirectional"))
    )
    (net (code "229") (name "unconnected-(U1H-PB13B{slash}CS1N-PadP8)") (class "Default")
      (node (ref "U1") (pin "P8") (pinfunction "PB13B/CS1N_P8") (pintype "bidirectional"))
    )
    (net (code "230") (name "unconnected-(U1H-PB15A{slash}HOLDN{slash}DI{slash}BUSY{slash}CSSPIN{slash}CEN-PadN8)") (class "Default")
      (node (ref "U1") (pin "N8") (pinfunction "PB15A/HOLDN/DI/BUSY/CSSPIN/CEN_N8") (pintype "bidirectional"))
    )
    (net (code "231") (name "unconnected-(U1H-PB15B{slash}DOUT{slash}CSON-PadM8)") (class "Default")
      (node (ref "U1") (pin "M8") (pinfunction "PB15B/DOUT/CSON_M8") (pintype "bidirectional"))
    )
    (net (code "232") (name "unconnected-(U1H-PB18A{slash}WRITEN-PadM9)") (class "Default")
      (node (ref "U1") (pin "M9") (pinfunction "PB18A/WRITEN_M9") (pintype "bidirectional"))
    )
    (net (code "233") (name "unconnected-(U1H-PROGRAMN-PadR9)") (class "Default")
      (node (ref "U1") (pin "R9") (pinfunction "PROGRAMN_R9") (pintype "bidirectional"))
    )
    (net (code "234") (name "unconnected-(Y1-N.C-Pad2)") (class "Default")
      (node (ref "Y1") (pin "2") (pinfunction "N.C_2") (pintype "passive+no_connect"))
    )
  )
)
